# LEDSystem_Triangle.net
KiCad netlist of a schematic drawn in EAGLE
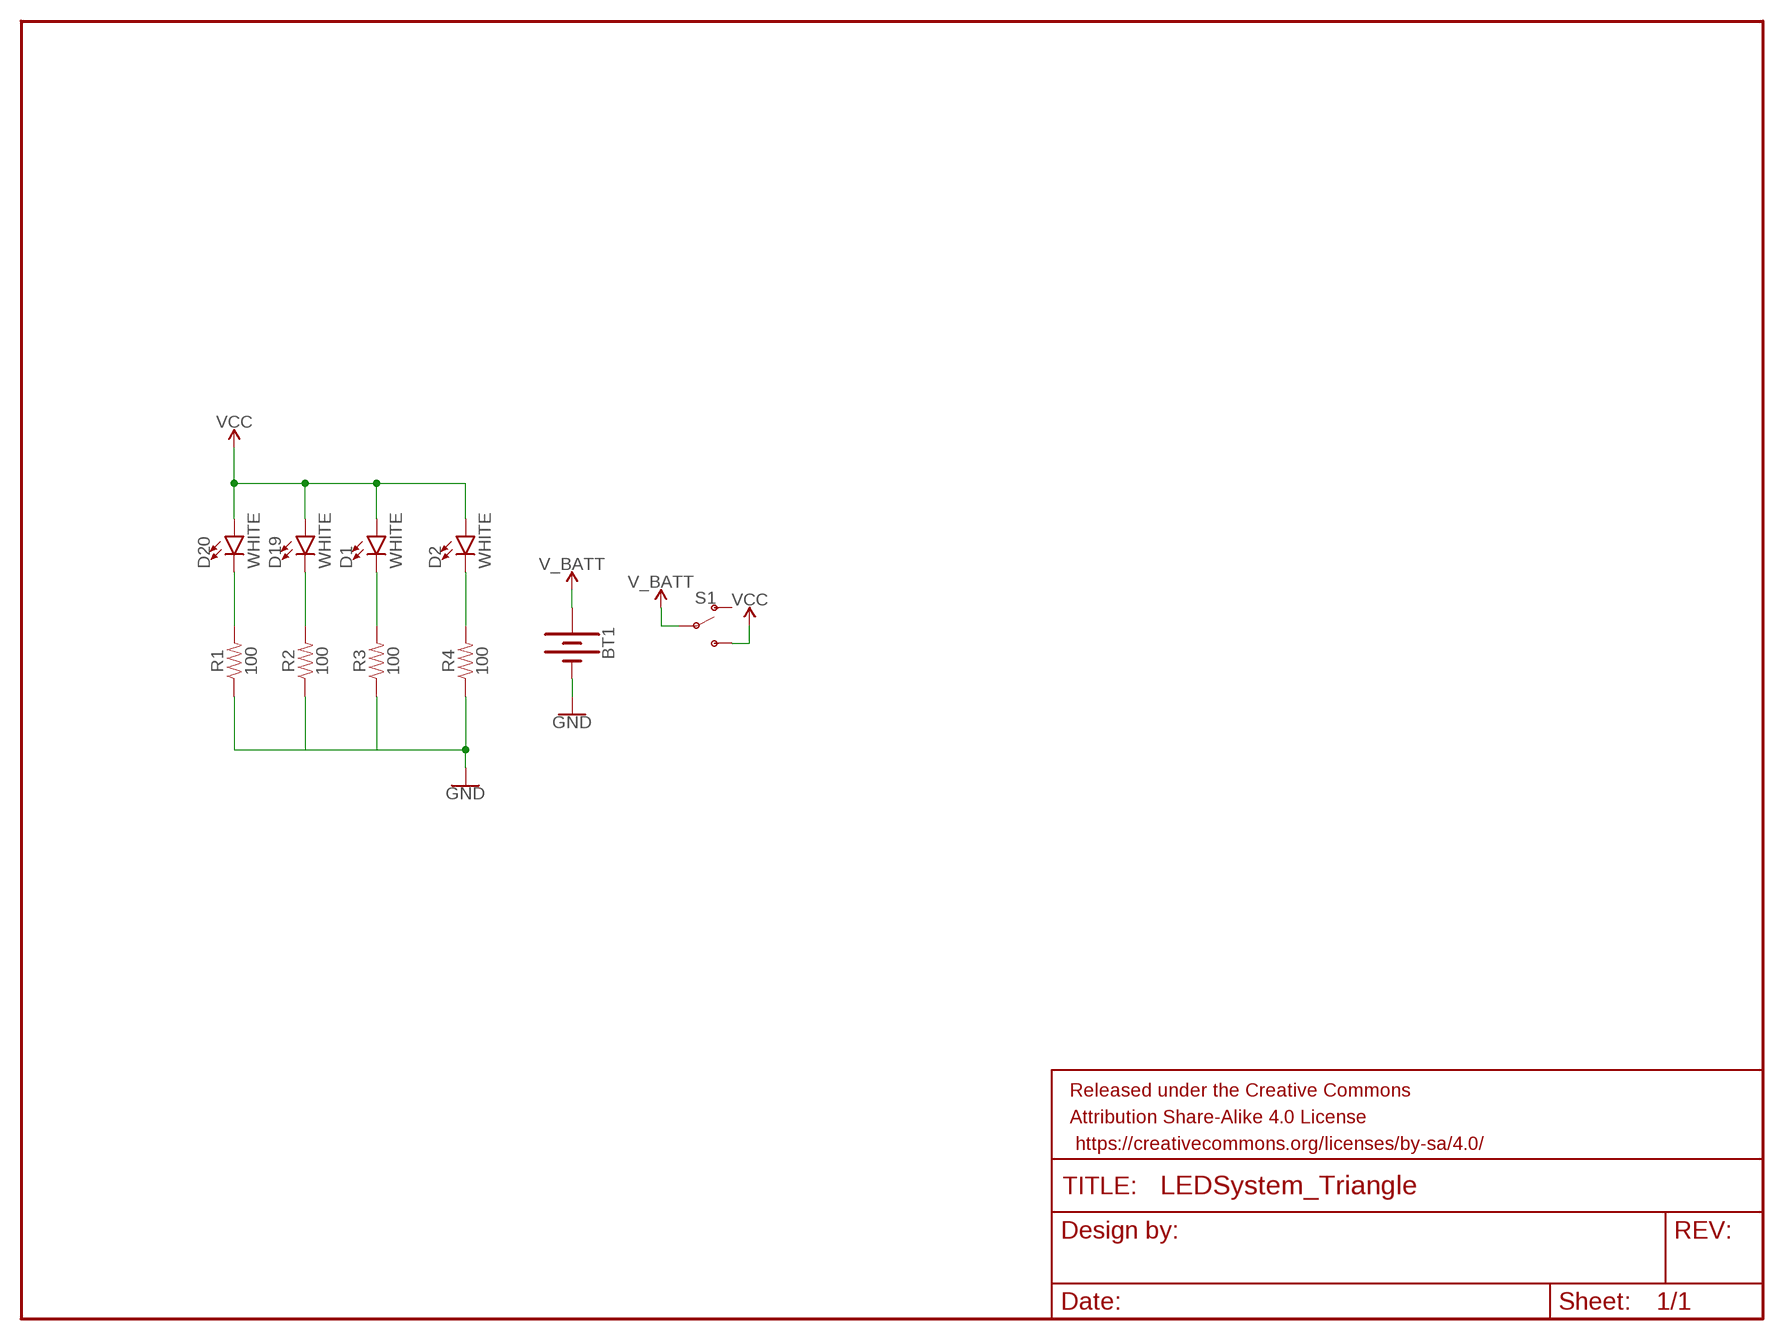
[diagram p0: schematic, sheet 1]

(export (version "E")
  (design (tool "Eeschema 10.0.6"))
  (components
    (comp (ref "BT1")
      (value "BATTERY-12MM_SMD")
      (footprint "eagle-import:BATTCON_12MM")
      (libsource (lib "eagle-import") (part "BATTERY-12MM_SMD"))
    )
    (comp (ref "D1")
      (value "WHITE")
      (footprint "eagle-import:LED-1206")
      (libsource (lib "eagle-import") (part "LED-WHITE1206"))
    )
    (comp (ref "D2")
      (value "WHITE")
      (footprint "eagle-import:LED-1206")
      (libsource (lib "eagle-import") (part "LED-WHITE1206"))
    )
    (comp (ref "D19")
      (value "WHITE")
      (footprint "eagle-import:LED-1206")
      (libsource (lib "eagle-import") (part "LED-WHITE1206"))
    )
    (comp (ref "D20")
      (value "WHITE")
      (footprint "eagle-import:LED-1206")
      (libsource (lib "eagle-import") (part "LED-WHITE1206"))
    )
    (comp (ref "FRAME1")
      (value "FRAME-LETTER")
      (footprint "eagle-import:CREATIVE_COMMONS")
      (libsource (lib "eagle-import") (part "FRAME-LETTER"))
    )
    (comp (ref "R1")
      (value "100")
      (footprint "eagle-import:0603")
      (libsource (lib "eagle-import") (part "100OHM-0603-1/4W-5%"))
    )
    (comp (ref "R2")
      (value "100")
      (footprint "eagle-import:0603")
      (libsource (lib "eagle-import") (part "100OHM-0603-1/4W-5%"))
    )
    (comp (ref "R3")
      (value "100")
      (footprint "eagle-import:0603")
      (libsource (lib "eagle-import") (part "100OHM-0603-1/4W-5%"))
    )
    (comp (ref "R4")
      (value "100")
      (footprint "eagle-import:0603")
      (libsource (lib "eagle-import") (part "100OHM-0603-1/4W-5%"))
    )
    (comp (ref "S1")
      (value "SWITCH-SPDT-SMD-RIGHT-ANGLE")
      (footprint "eagle-import:SWITCH_SPST_SMD_A")
      (libsource (lib "eagle-import") (part "SWITCH-SPDT-SMD-RIGHT-ANGLE"))
    )
  )
  (nets
    (net (code "1") (name "GND") (class "Default")
      (node (ref "BT1") (pin "GND") (pinfunction "-_GND") (pintype "power_in"))
      (node (ref "R1") (pin "1") (pinfunction "1_1") (pintype "passive"))
      (node (ref "R2") (pin "1") (pinfunction "1_1") (pintype "passive"))
      (node (ref "R3") (pin "1") (pinfunction "1_1") (pintype "passive"))
      (node (ref "R4") (pin "1") (pinfunction "1_1") (pintype "passive"))
    )
    (net (code "2") (name "Net-(D1-PadC)") (class "Default")
      (node (ref "D1") (pin "C") (pinfunction "C_C") (pintype "passive"))
      (node (ref "R3") (pin "2") (pinfunction "2_2") (pintype "passive"))
    )
    (net (code "3") (name "Net-(D2-PadC)") (class "Default")
      (node (ref "D2") (pin "C") (pinfunction "C_C") (pintype "passive"))
      (node (ref "R4") (pin "2") (pinfunction "2_2") (pintype "passive"))
    )
    (net (code "4") (name "Net-(D19-PadC)") (class "Default")
      (node (ref "D19") (pin "C") (pinfunction "C_C") (pintype "passive"))
      (node (ref "R2") (pin "2") (pinfunction "2_2") (pintype "passive"))
    )
    (net (code "5") (name "Net-(D20-PadC)") (class "Default")
      (node (ref "D20") (pin "C") (pinfunction "C_C") (pintype "passive"))
      (node (ref "R1") (pin "2") (pinfunction "2_2") (pintype "passive"))
    )
    (net (code "6") (name "VCC") (class "Default")
      (node (ref "D1") (pin "A") (pinfunction "A_A") (pintype "passive"))
      (node (ref "D19") (pin "A") (pinfunction "A_A") (pintype "passive"))
      (node (ref "D2") (pin "A") (pinfunction "A_A") (pintype "passive"))
      (node (ref "D20") (pin "A") (pinfunction "A_A") (pintype "passive"))
      (node (ref "S1") (pin "3") (pinfunction "S_3") (pintype "passive"))
    )
    (net (code "7") (name "V_BATT") (class "Default")
      (node (ref "BT1") (pin "PWR@1") (pinfunction "+_PWR@1") (pintype "power_in"))
      (node (ref "S1") (pin "2") (pinfunction "P_2") (pintype "passive"))
    )
    (net (code "8") (name "unconnected-(S1-O-Pad1)") (class "Default")
      (node (ref "S1") (pin "1") (pinfunction "O_1") (pintype "passive"))
    )
  )
)
